# 1_V2.net
KiCad netlist of a schematic drawn in Altium Designer
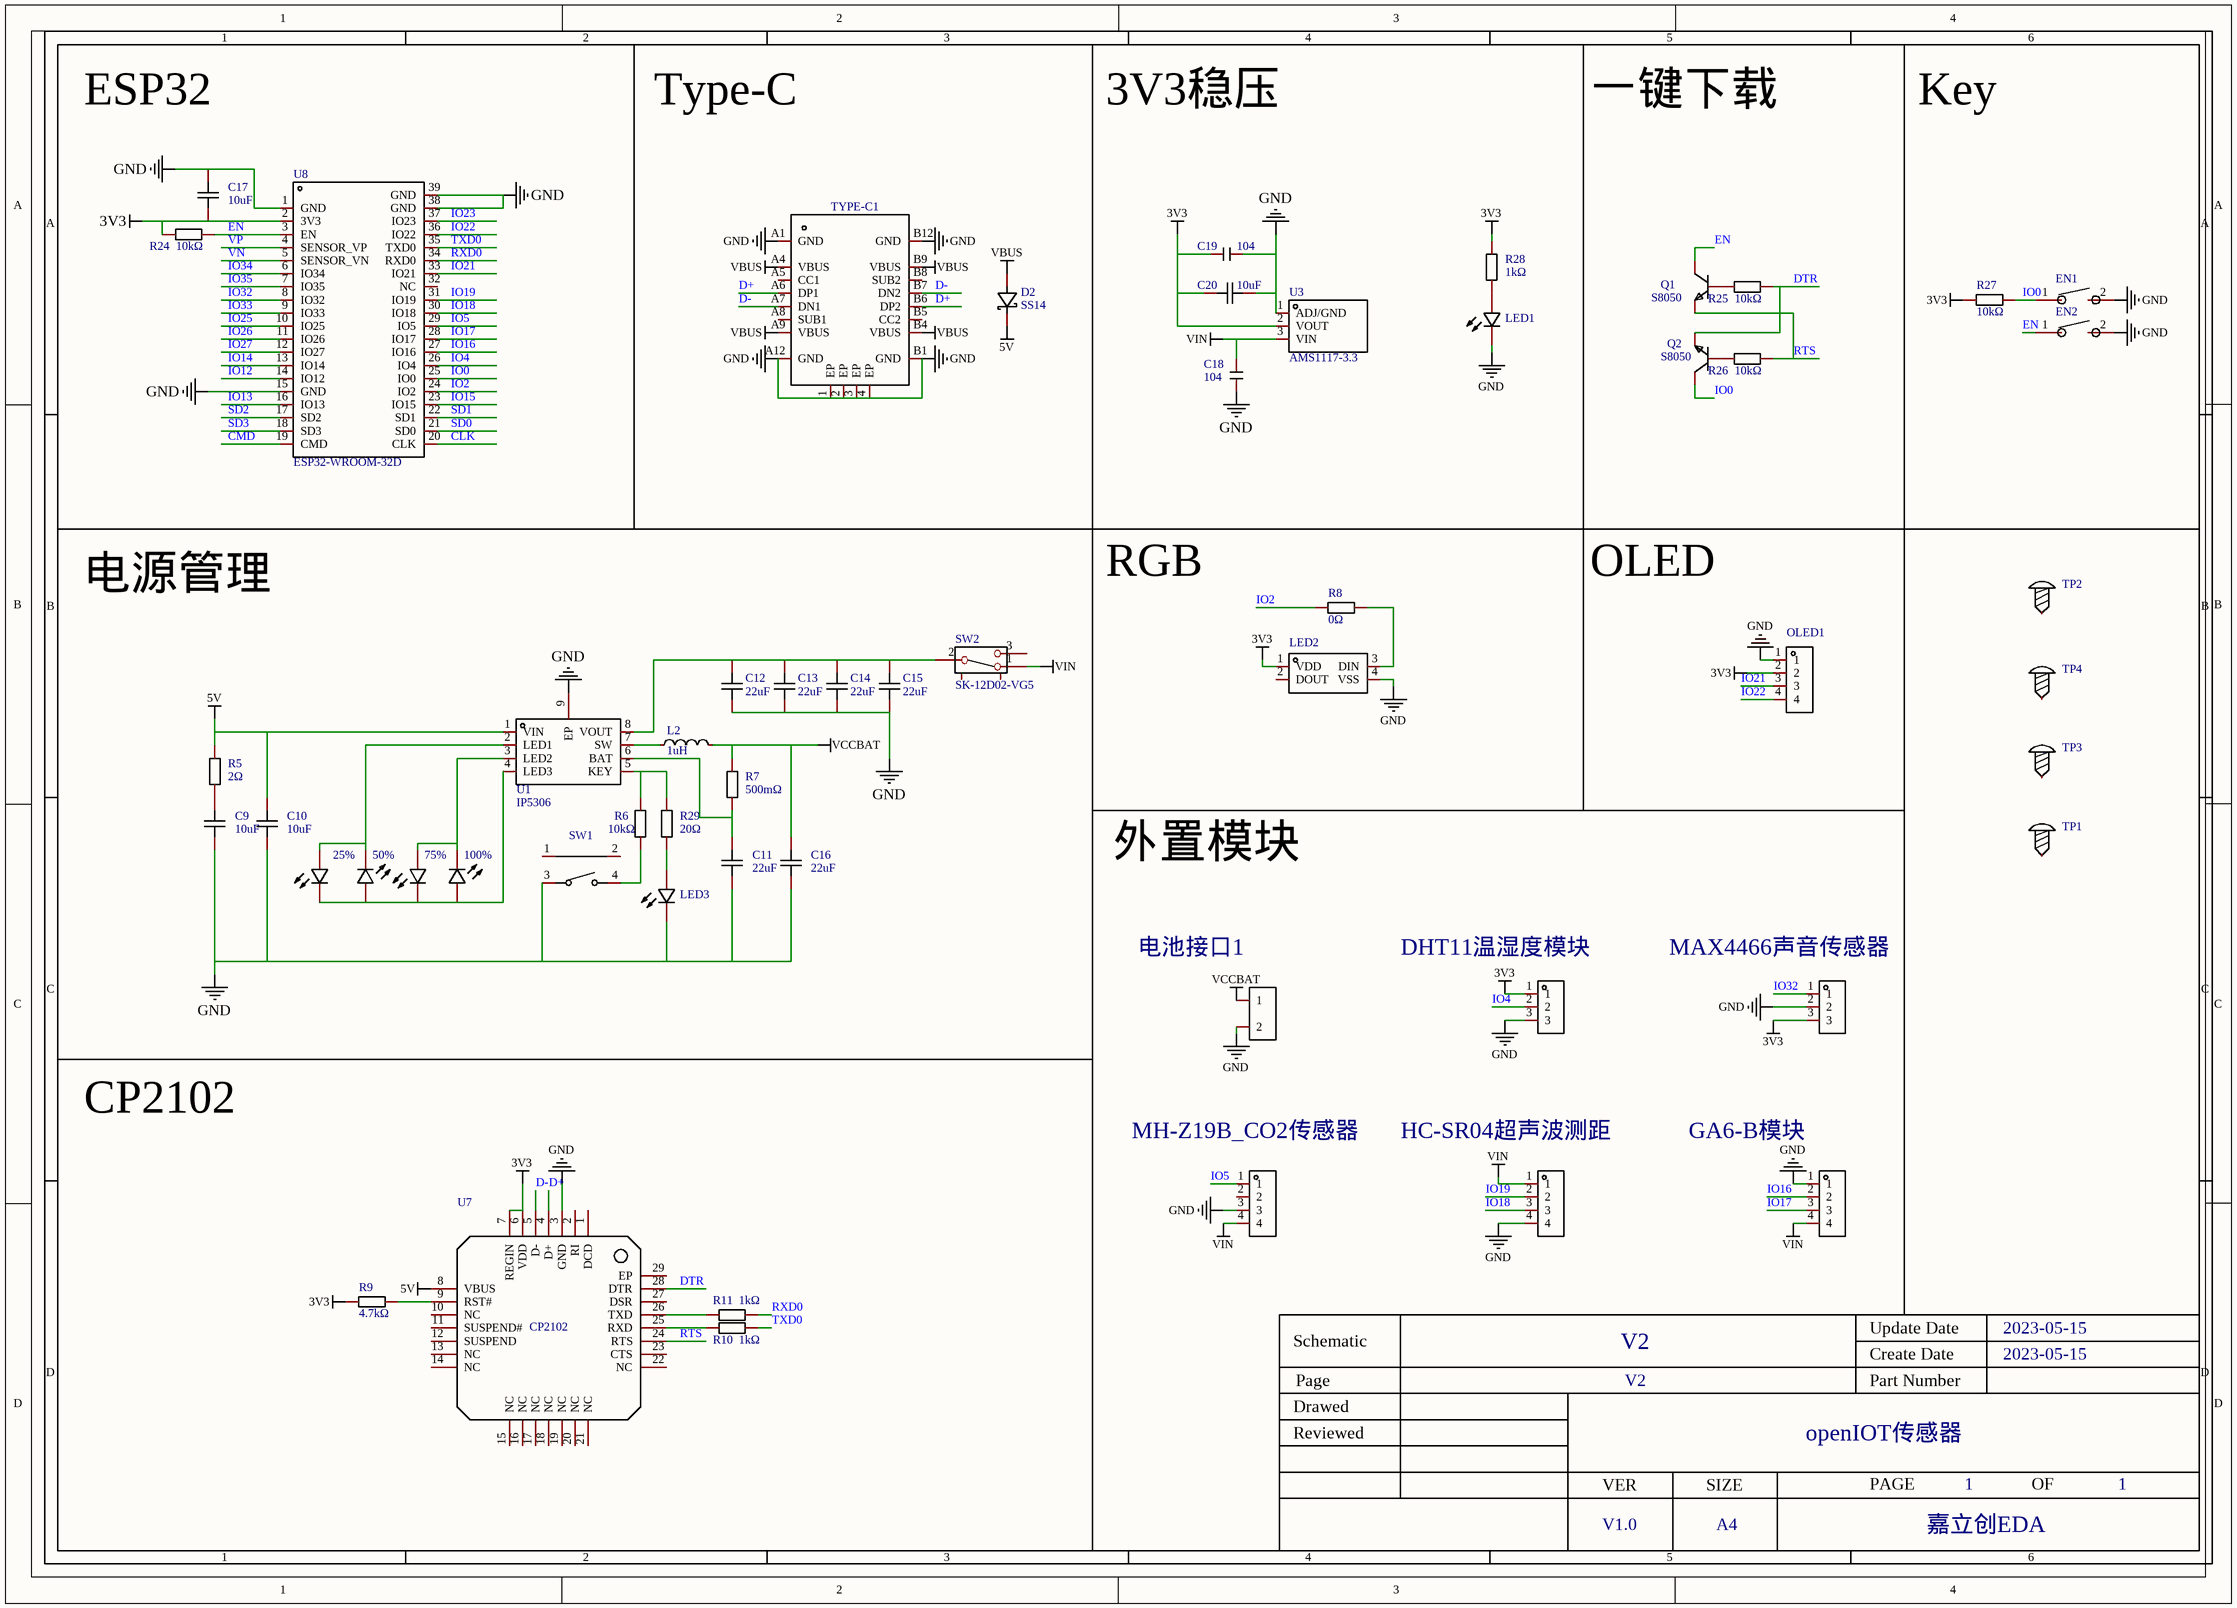
[diagram p0: 1_V2.schdoc]

(export (version "E")
  (design (tool "Eeschema 10.0.6"))
  (components
    (comp (ref "25%")
      (value "19-217/GHC-YR1S2/3T")
      (description "发光颜色:翠绿;二极管配置:-;主波长:520nm~535nm;色温:-;功率:110mW;安装方式:-;")
      (fields (field (name "MANUFACTURER") "EVERLIGHT(亿光)"))
      (libsource (lib "altium-import") (part "root_1_19-217/GHC-YR1S2/3T_"))
    )
    (comp (ref "50%")
      (value "19-217/GHC-YR1S2/3T")
      (description "发光颜色:翠绿;二极管配置:-;主波长:520nm~535nm;色温:-;功率:110mW;安装方式:-;")
      (fields (field (name "MANUFACTURER") "EVERLIGHT(亿光)"))
      (libsource (lib "altium-import") (part "root_3_19-217/GHC-YR1S2/3T_"))
    )
    (comp (ref "75%")
      (value "19-217/GHC-YR1S2/3T")
      (description "发光颜色:翠绿;二极管配置:-;主波长:520nm~535nm;色温:-;功率:110mW;安装方式:-;")
      (fields (field (name "MANUFACTURER") "EVERLIGHT(亿光)"))
      (libsource (lib "altium-import") (part "root_1_19-217/GHC-YR1S2/3T_"))
    )
    (comp (ref "100%")
      (value "19-217/GHC-YR1S2/3T")
      (description "发光颜色:翠绿;二极管配置:-;主波长:520nm~535nm;色温:-;功率:110mW;安装方式:-;")
      (fields (field (name "MANUFACTURER") "EVERLIGHT(亿光)"))
      (libsource (lib "altium-import") (part "root_3_19-217/GHC-YR1S2/3T_"))
    )
    (comp (ref "C9")
      (value "10uF")
      (description "容值:10uF;精度:±10%;额定电压:50V;材质(温度系数):X5R;")
      (fields
        (field (name "NAME") "10uF")
        (field (name "MANUFACTURER") "muRata(村田)")
        (field (name "MANUFACTURER PART") "GRM21BR61H106KE43L")
      )
      (libsource (lib "altium-import") (part "root_1_GRM21BR61H106KE43L_"))
    )
    (comp (ref "C10")
      (value "10uF")
      (description "容值:10uF;精度:±10%;额定电压:50V;材质(温度系数):X5R;")
      (fields
        (field (name "NAME") "10uF")
        (field (name "MANUFACTURER") "muRata(村田)")
        (field (name "MANUFACTURER PART") "GRM21BR61H106KE43L")
      )
      (libsource (lib "altium-import") (part "root_1_GRM21BR61H106KE43L_"))
    )
    (comp (ref "C11")
      (value "22uF")
      (description "容值:22uF;精度:±20%;额定电压:35V;材质(温度系数):X5R;")
      (fields
        (field (name "NAME") "22uF")
        (field (name "MANUFACTURER") "TDK")
        (field (name "MANUFACTURER PART") "C3216X5R1V226MTJ00E")
      )
      (libsource (lib "altium-import") (part "root_0_C3216X5R1V226MTJ00E_"))
    )
    (comp (ref "C12")
      (value "22uF")
      (description "容值:22uF;精度:±20%;额定电压:35V;材质(温度系数):X5R;")
      (fields
        (field (name "NAME") "22uF")
        (field (name "MANUFACTURER") "TDK")
        (field (name "MANUFACTURER PART") "C3216X5R1V226MTJ00E")
      )
      (libsource (lib "altium-import") (part "root_0_C3216X5R1V226MTJ00E_"))
    )
    (comp (ref "C13")
      (value "22uF")
      (description "容值:22uF;精度:±20%;额定电压:35V;材质(温度系数):X5R;")
      (fields
        (field (name "NAME") "22uF")
        (field (name "MANUFACTURER") "TDK")
        (field (name "MANUFACTURER PART") "C3216X5R1V226MTJ00E")
      )
      (libsource (lib "altium-import") (part "root_0_C3216X5R1V226MTJ00E_"))
    )
    (comp (ref "C14")
      (value "22uF")
      (description "容值:22uF;精度:±20%;额定电压:35V;材质(温度系数):X5R;")
      (fields
        (field (name "NAME") "22uF")
        (field (name "MANUFACTURER") "TDK")
        (field (name "MANUFACTURER PART") "C3216X5R1V226MTJ00E")
      )
      (libsource (lib "altium-import") (part "root_0_C3216X5R1V226MTJ00E_"))
    )
    (comp (ref "C15")
      (value "22uF")
      (description "容值:22uF;精度:±20%;额定电压:35V;材质(温度系数):X5R;")
      (fields
        (field (name "NAME") "22uF")
        (field (name "MANUFACTURER") "TDK")
        (field (name "MANUFACTURER PART") "C3216X5R1V226MTJ00E")
      )
      (libsource (lib "altium-import") (part "root_0_C3216X5R1V226MTJ00E_"))
    )
    (comp (ref "C16")
      (value "22uF")
      (description "容值:22uF;精度:±20%;额定电压:35V;材质(温度系数):X5R;")
      (fields
        (field (name "NAME") "22uF")
        (field (name "MANUFACTURER") "TDK")
        (field (name "MANUFACTURER PART") "C3216X5R1V226MTJ00E")
      )
      (libsource (lib "altium-import") (part "root_0_C3216X5R1V226MTJ00E_"))
    )
    (comp (ref "C17")
      (value "10uF")
      (description "容值:10uF;精度:±10%;额定电压:50V;材质(温度系数):X5R;")
      (fields
        (field (name "NAME") "10uF")
        (field (name "MANUFACTURER") "muRata(村田)")
        (field (name "MANUFACTURER PART") "GRM21BR61H106KE43L")
      )
      (libsource (lib "altium-import") (part "root_1_GRM21BR61H106KE43L_"))
    )
    (comp (ref "C18")
      (value "104")
      (fields (field (name "NAME") "104") (field (name "版权归属") "源创客"))
      (libsource (lib "altium-import") (part "root_1_104_"))
    )
    (comp (ref "C19")
      (value "104")
      (fields (field (name "NAME") "104") (field (name "版权归属") "源创客"))
      (libsource (lib "altium-import") (part "root_2_104_"))
    )
    (comp (ref "C20")
      (value "10uF")
      (description "容值:10uF;精度:±10%;额定电压:50V;材质(温度系数):X5R;")
      (fields
        (field (name "NAME") "10uF")
        (field (name "MANUFACTURER") "muRata(村田)")
        (field (name "MANUFACTURER PART") "GRM21BR61H106KE43L")
      )
      (libsource (lib "altium-import") (part "root_2_GRM21BR61H106KE43L_"))
    )
    (comp (ref "D2")
      (value "SS14")
      (description "二极管配置:-;直流反向耐压(Vr):40V;平均整流电流(Io):1A;正向压降(Vf):550mV@1A;反向电流(Ir):500uA@40V;")
      (fields (field (name "NAME") "SS14") (field (name "MANUFACTURER") "KUU"))
      (libsource (lib "altium-import") (part "root_1_SS14_C2909920_"))
    )
    (comp (ref "DHT11温湿度模块")
      (value "B-2200S03P-A120")
      (description "排数:单排;总孔位数:3;间距:2.54mm;插孔结构:1x3P;行距:-;安装类型:直插;塑高:-;触头材质:黄铜;触头镀层:-;")
      (fields (field (name "MANUFACTURER") "Ckmtw(灿科盟)"))
      (libsource (lib "altium-import") (part "root_0_B-2200S03P-A120_"))
    )
    (comp (ref "EN1")
      (value "TSA343G00-250J2")
      (fields (field (name "MANUFACTURER") "BRIGHT(博瑞泰)"))
      (libsource (lib "altium-import") (part "root_0_TSA343G00-250J2_"))
    )
    (comp (ref "EN2")
      (value "TSA343G00-250J2")
      (fields (field (name "MANUFACTURER") "BRIGHT(博瑞泰)"))
      (libsource (lib "altium-import") (part "root_0_TSA343G00-250J2_"))
    )
    (comp (ref "GA6-B模块")
      (value "2.54-1*4P母")
      (fields (field (name "MANUFACTURER") "BOOMELE(博穆精密)"))
      (libsource (lib "altium-import") (part "root_0_2.54-1*4P母_"))
    )
    (comp (ref "HC-SR04超声波测距")
      (value "2.54-1*4P母")
      (fields (field (name "MANUFACTURER") "BOOMELE(博穆精密)"))
      (libsource (lib "altium-import") (part "root_0_2.54-1*4P母_"))
    )
    (comp (ref "L2")
      (value "1uH")
      (description "电感值:1uH;精度:±20%;额定电流:8.5A;饱和电流(Isat):14A;")
      (fields
        (field (name "NAME") "1uH")
        (field (name "MANUFACTURER") "cjiang(长江微电)")
        (field (name "MANUFACTURER PART") "FXL0618-1R0-M")
      )
      (libsource (lib "altium-import") (part "root_0_FXL0618-1R0-M_"))
    )
    (comp (ref "LED1")
      (value "19-217/GHC-YR1S2/3T")
      (description "发光颜色:翠绿;二极管配置:-;主波长:520nm~535nm;色温:-;功率:110mW;安装方式:-;")
      (fields (field (name "MANUFACTURER") "EVERLIGHT(亿光)"))
      (libsource (lib "altium-import") (part "root_1_19-217/GHC-YR1S2/3T_"))
    )
    (comp (ref "LED2")
      (value "WS2812B-V5/W")
      (fields (field (name "MANUFACTURER") "worldsemi"))
      (libsource (lib "altium-import") (part "root_0_WS2812B-V5/W_"))
    )
    (comp (ref "LED3")
      (value "19-217/GHC-YR1S2/3T")
      (description "发光颜色:翠绿;二极管配置:-;主波长:520nm~535nm;色温:-;功率:110mW;安装方式:-;")
      (fields (field (name "MANUFACTURER") "EVERLIGHT(亿光)"))
      (libsource (lib "altium-import") (part "root_1_19-217/GHC-YR1S2/3T_"))
    )
    (comp (ref "MAX4466声音传感器")
      (value "B-2200S03P-A120")
      (description "排数:单排;总孔位数:3;间距:2.54mm;插孔结构:1x3P;行距:-;安装类型:直插;塑高:-;触头材质:黄铜;触头镀层:-;")
      (fields (field (name "MANUFACTURER") "Ckmtw(灿科盟)"))
      (libsource (lib "altium-import") (part "root_0_B-2200S03P-A120_"))
    )
    (comp (ref "MH-Z19B_CO2传感器")
      (value "2.54-1*4P母")
      (fields (field (name "MANUFACTURER") "BOOMELE(博穆精密)"))
      (libsource (lib "altium-import") (part "root_0_2.54-1*4P母_"))
    )
    (comp (ref "OLED1")
      (value "2.54-1*4P母")
      (fields (field (name "MANUFACTURER") "BOOMELE(博穆精密)"))
      (libsource (lib "altium-import") (part "root_0_2.54-1*4P母_"))
    )
    (comp (ref "Q1")
      (value "S8050")
      (fields (field (name "NAME") "S8050") (field (name "MANUFACTURER") "WPMtek(维攀微)"))
      (libsource (lib "altium-import") (part "root_0_S8050_"))
    )
    (comp (ref "Q2")
      (value "S8050")
      (fields (field (name "NAME") "S8050") (field (name "MANUFACTURER") "WPMtek(维攀微)"))
      (libsource (lib "altium-import") (part "root_2_S8050_"))
    )
    (comp (ref "R5")
      (value "2Ω")
      (description "电阻类型:厚膜电阻;阻值:2Ω;精度:±1%;功率:125mW;")
      (fields
        (field (name "NAME") "2Ω")
        (field (name "MANUFACTURER") "UNI-ROYAL(厚声)")
        (field (name "MANUFACTURER PART") "0805W8F200KT5E")
      )
      (libsource (lib "altium-import") (part "root_1_0805W8F200KT5E_"))
    )
    (comp (ref "R6")
      (value "10kΩ")
      (description "电阻类型:厚膜电阻;阻值:10kΩ;精度:±1%;功率:125mW;")
      (fields
        (field (name "NAME") "10kΩ")
        (field (name "MANUFACTURER") "UNI-ROYAL(厚声)")
        (field (name "MANUFACTURER PART") "0805W8F1002T5E")
      )
      (libsource (lib "altium-import") (part "root_1_0805W8F1002T5E_C17414_"))
    )
    (comp (ref "R7")
      (value "500mΩ")
      (description "电阻类型:厚膜电阻;阻值:500mΩ;精度:±1%;功率:250mW;")
      (fields
        (field (name "NAME") "500mΩ")
        (field (name "MANUFACTURER") "UNI-ROYAL(厚声)")
        (field (name "MANUFACTURER PART") "1206W4F500LT5E")
      )
      (libsource (lib "altium-import") (part "root_1_1206W4F500LT5E_"))
    )
    (comp (ref "R8")
      (value "0Ω")
      (description "电阻类型:厚膜电阻;阻值:0Ω;精度:±1%;功率:100mW;最大工作电压:75V;工作温度范围:-55℃~+155℃;")
      (fields
        (field (name "MANUFACTURER") "UNI-ROYAL(厚声)")
        (field (name "MANUFACTURER PART") "0603WAF0000T5E")
      )
      (libsource (lib "altium-import") (part "root_2_0603WAF0000T5E_"))
    )
    (comp (ref "R9")
      (value "4.7kΩ")
      (description "电阻类型:厚膜电阻;阻值:4.7kΩ;精度:±1%;功率:100mW;")
      (fields
        (field (name "NAME") "4.7kΩ")
        (field (name "MANUFACTURER") "UNI-ROYAL(厚声)")
        (field (name "MANUFACTURER PART") "0603WAF4701T5E")
      )
      (libsource (lib "altium-import") (part "root_0_0603WAF4701T5E_"))
    )
    (comp (ref "R10")
      (value "1kΩ")
      (description "电阻类型:厚膜电阻;阻值:1kΩ;精度:±1%;功率:100mW;")
      (fields
        (field (name "NAME") "1kΩ")
        (field (name "MANUFACTURER") "UNI-ROYAL(厚声)")
        (field (name "MANUFACTURER PART") "0603WAF1001T5E")
      )
      (libsource (lib "altium-import") (part "root_0_0603WAF1001T5E_"))
    )
    (comp (ref "R11")
      (value "1kΩ")
      (description "电阻类型:厚膜电阻;阻值:1kΩ;精度:±1%;功率:100mW;")
      (fields
        (field (name "NAME") "1kΩ")
        (field (name "MANUFACTURER") "UNI-ROYAL(厚声)")
        (field (name "MANUFACTURER PART") "0603WAF1001T5E")
      )
      (libsource (lib "altium-import") (part "root_0_0603WAF1001T5E_"))
    )
    (comp (ref "R24")
      (value "10kΩ")
      (description "电阻类型:厚膜电阻;阻值:10kΩ;精度:±1%;功率:100mW;")
      (fields
        (field (name "NAME") "10kΩ")
        (field (name "MANUFACTURER") "UNI-ROYAL(厚声)")
        (field (name "MANUFACTURER PART") "0603WAF1002T5E")
      )
      (libsource (lib "altium-import") (part "root_0_0603WAF1002T5E_"))
    )
    (comp (ref "R25")
      (value "10kΩ")
      (description "电阻类型:厚膜电阻;阻值:10kΩ;精度:±1%;功率:100mW;")
      (fields
        (field (name "NAME") "10kΩ")
        (field (name "MANUFACTURER") "UNI-ROYAL(厚声)")
        (field (name "MANUFACTURER PART") "0603WAF1002T5E")
      )
      (libsource (lib "altium-import") (part "root_0_0603WAF1002T5E_"))
    )
    (comp (ref "R26")
      (value "10kΩ")
      (description "电阻类型:厚膜电阻;阻值:10kΩ;精度:±1%;功率:100mW;")
      (fields
        (field (name "NAME") "10kΩ")
        (field (name "MANUFACTURER") "UNI-ROYAL(厚声)")
        (field (name "MANUFACTURER PART") "0603WAF1002T5E")
      )
      (libsource (lib "altium-import") (part "root_0_0603WAF1002T5E_"))
    )
    (comp (ref "R27")
      (value "10kΩ")
      (description "电阻类型:厚膜电阻;阻值:10kΩ;精度:±1%;功率:100mW;")
      (fields
        (field (name "NAME") "10kΩ")
        (field (name "MANUFACTURER") "UNI-ROYAL(厚声)")
        (field (name "MANUFACTURER PART") "0603WAF1002T5E")
      )
      (libsource (lib "altium-import") (part "root_2_0603WAF1002T5E_"))
    )
    (comp (ref "R28")
      (value "1kΩ")
      (description "电阻类型:厚膜电阻;阻值:1kΩ;精度:±1%;功率:100mW;")
      (fields
        (field (name "NAME") "1kΩ")
        (field (name "MANUFACTURER") "UNI-ROYAL(厚声)")
        (field (name "MANUFACTURER PART") "0603WAF1001T5E")
      )
      (libsource (lib "altium-import") (part "root_1_0603WAF1001T5E_"))
    )
    (comp (ref "R29")
      (value "20Ω")
      (description "电阻类型:厚膜电阻;阻值:20Ω;精度:±1%;功率:100mW;")
      (fields
        (field (name "NAME") "20Ω")
        (field (name "MANUFACTURER") "UNI-ROYAL(厚声)")
        (field (name "MANUFACTURER PART") "0603WAF200JT5E")
      )
      (libsource (lib "altium-import") (part "root_1_0603WAF200JT5E_"))
    )
    (comp (ref "SW1")
      (value "TS24CA")
      (description "触点电流:50mA;额定电压(DC):12V;电路结构:单刀单掷;安装方式:卧贴;带灯:-;机械寿命:-;")
      (fields (field (name "MANUFACTURER") "SHOU HAN(首韩)"))
      (libsource (lib "altium-import") (part "root_0_TS24CA_"))
    )
    (comp (ref "SW2")
      (value "SK-12D02-VG5")
      (fields (field (name "NAME") "SK-12D02-VG5") (field (name "MANUFACTURER") "韩国韩荣"))
      (libsource (lib "altium-import") (part "root_0_SK-12D02-VG5_C136722_"))
    )
    (comp (ref "TP1") (value "M2螺丝") (libsource (lib "altium-import") (part "root_0_M2螺丝_")))
    (comp (ref "TP2") (value "M2螺丝") (libsource (lib "altium-import") (part "root_0_M2螺丝_")))
    (comp (ref "TP3") (value "M2螺丝") (libsource (lib "altium-import") (part "root_0_M2螺丝_")))
    (comp (ref "TP4") (value "M2螺丝") (libsource (lib "altium-import") (part "root_0_M2螺丝_")))
    (comp (ref "TYPE-C1")
      (value "KH-TYPE-C-16P")
      (description "连接器类型:Type-C;标准:-;公母:母座;触点数量:16;端口数量:1;安装方式:卧贴;额定电流 - 电源:3A;工作温度范围:-40℃~+85℃;")
      (fields (field (name "MANUFACTURER") "kinghelm(金航标)"))
      (libsource (lib "altium-import") (part "root_0_KH-TYPE-C-16P_"))
    )
    (comp (ref "U1")
      (value "IP5306")
      (description "2.1A充电2.4A放电高集成度移动电源SOC")
      (fields (field (name "NAME") "IP5306") (field (name "MANUFACTURER") "INJOINIC(英集芯)"))
      (libsource (lib "altium-import") (part "root_0_IP5306_"))
    )
    (comp (ref "U3")
      (value "AMS1117-3.3")
      (description "输出类型:-;")
      (fields (field (name "NAME") "AMS1117-3.3") (field (name "MANUFACTURER") "Slkor(萨科微)"))
      (libsource (lib "altium-import") (part "root_0_AMS1117-3.3_C880752_"))
    )
    (comp (ref "U7")
      (value "CP2102")
      (description "类型:Transceiver;协议类别:USB;驱动器/接收器数:1/1;数据速率:1Mbps;")
      (fields (field (name "NAME") "CP2102") (field (name "MANUFACTURER") "SILICON LABS(芯科)"))
      (libsource (lib "altium-import") (part "root_3_CP2102-GMR_"))
    )
    (comp (ref "U8")
      (value "ESP32-WROOM-32D")
      (fields (field (name "NAME") "ESP32-WROOM-32D"))
      (libsource (lib "altium-import") (part "root_0_ESP32-WROOM-32D_"))
    )
    (comp (ref "电池接口1")
      (value "826629-2")
      (fields (field (name "MANUFACTURER") "TE Connectivity(美国泰科)"))
      (libsource (lib "altium-import") (part "root_0_826629-2_"))
    )
  )
  (nets
    (net (code "1") (name "/CLK") (class "Default")
      (node (ref "U8") (pin "20") (pinfunction "CLK_20") (pintype "passive"))
    )
    (net (code "2") (name "/CMD") (class "Default")
      (node (ref "U8") (pin "19") (pinfunction "CMD_19") (pintype "passive"))
    )
    (net (code "3") (name "/D+") (class "Default")
      (node (ref "TYPE-C1") (pin "A6") (pinfunction "DP1_A6") (pintype "passive"))
      (node (ref "TYPE-C1") (pin "B6") (pinfunction "DP2_B6") (pintype "passive"))
      (node (ref "U7") (pin "4") (pinfunction "D+_4") (pintype "passive"))
    )
    (net (code "4") (name "/D-") (class "Default")
      (node (ref "TYPE-C1") (pin "A7") (pinfunction "DN1_A7") (pintype "passive"))
      (node (ref "TYPE-C1") (pin "B7") (pinfunction "DN2_B7") (pintype "passive"))
      (node (ref "U7") (pin "5") (pinfunction "D-_5") (pintype "passive"))
    )
    (net (code "5") (name "/DTR") (class "Default")
      (node (ref "Q2") (pin "2") (pinfunction "E_2") (pintype "passive"))
      (node (ref "R25") (pin "2") (pinfunction "2_2") (pintype "passive"))
      (node (ref "U7") (pin "28") (pinfunction "DTR_28") (pintype "passive"))
    )
    (net (code "6") (name "/EN") (class "Default")
      (node (ref "EN2") (pin "1") (pinfunction "1_1") (pintype "passive"))
      (node (ref "Q1") (pin "3") (pinfunction "C_3") (pintype "passive"))
      (node (ref "R24") (pin "2") (pinfunction "2_2") (pintype "passive"))
      (node (ref "U8") (pin "3") (pinfunction "EN_3") (pintype "passive"))
    )
    (net (code "7") (name "/IO0") (class "Default")
      (node (ref "EN1") (pin "1") (pinfunction "1_1") (pintype "passive"))
      (node (ref "Q2") (pin "3") (pinfunction "C_3") (pintype "passive"))
      (node (ref "R27") (pin "1") (pinfunction "1_1") (pintype "passive"))
      (node (ref "U8") (pin "25") (pinfunction "IO0_25") (pintype "passive"))
    )
    (net (code "8") (name "/IO2") (class "Default")
      (node (ref "R8") (pin "2") (pinfunction "2_2") (pintype "passive"))
      (node (ref "U8") (pin "24") (pinfunction "IO2_24") (pintype "passive"))
    )
    (net (code "9") (name "/IO4") (class "Default")
      (node (ref "DHT11温湿度模块") (pin "2") (pinfunction "2_2") (pintype "passive"))
      (node (ref "U8") (pin "26") (pinfunction "IO4_26") (pintype "passive"))
    )
    (net (code "10") (name "/IO5") (class "Default")
      (node (ref "MH-Z19B_CO2传感器") (pin "1") (pinfunction "1_1") (pintype "passive"))
      (node (ref "U8") (pin "29") (pinfunction "IO5_29") (pintype "passive"))
    )
    (net (code "11") (name "/IO12") (class "Default")
      (node (ref "U8") (pin "14") (pinfunction "IO12_14") (pintype "passive"))
    )
    (net (code "12") (name "/IO13") (class "Default")
      (node (ref "U8") (pin "16") (pinfunction "IO13_16") (pintype "passive"))
    )
    (net (code "13") (name "/IO14") (class "Default")
      (node (ref "U8") (pin "13") (pinfunction "IO14_13") (pintype "passive"))
    )
    (net (code "14") (name "/IO15") (class "Default")
      (node (ref "U8") (pin "23") (pinfunction "IO15_23") (pintype "passive"))
    )
    (net (code "15") (name "/IO16") (class "Default")
      (node (ref "GA6-B模块") (pin "2") (pinfunction "2_2") (pintype "passive"))
      (node (ref "U8") (pin "27") (pinfunction "IO16_27") (pintype "passive"))
    )
    (net (code "16") (name "/IO17") (class "Default")
      (node (ref "GA6-B模块") (pin "3") (pinfunction "3_3") (pintype "passive"))
      (node (ref "U8") (pin "28") (pinfunction "IO17_28") (pintype "passive"))
    )
    (net (code "17") (name "/IO18") (class "Default")
      (node (ref "HC-SR04超声波测距") (pin "3") (pinfunction "3_3") (pintype "passive"))
      (node (ref "U8") (pin "30") (pinfunction "IO18_30") (pintype "passive"))
    )
    (net (code "18") (name "/IO19") (class "Default")
      (node (ref "HC-SR04超声波测距") (pin "2") (pinfunction "2_2") (pintype "passive"))
      (node (ref "U8") (pin "31") (pinfunction "IO19_31") (pintype "passive"))
    )
    (net (code "19") (name "/IO21") (class "Default")
      (node (ref "OLED1") (pin "3") (pinfunction "3_3") (pintype "passive"))
      (node (ref "U8") (pin "33") (pinfunction "IO21_33") (pintype "passive"))
    )
    (net (code "20") (name "/IO22") (class "Default")
      (node (ref "OLED1") (pin "4") (pinfunction "4_4") (pintype "passive"))
      (node (ref "U8") (pin "36") (pinfunction "IO22_36") (pintype "passive"))
    )
    (net (code "21") (name "/IO23") (class "Default")
      (node (ref "U8") (pin "37") (pinfunction "IO23_37") (pintype "passive"))
    )
    (net (code "22") (name "/IO25") (class "Default")
      (node (ref "U8") (pin "10") (pinfunction "IO25_10") (pintype "passive"))
    )
    (net (code "23") (name "/IO26") (class "Default")
      (node (ref "U8") (pin "11") (pinfunction "IO26_11") (pintype "passive"))
    )
    (net (code "24") (name "/IO27") (class "Default")
      (node (ref "U8") (pin "12") (pinfunction "IO27_12") (pintype "passive"))
    )
    (net (code "25") (name "/IO32") (class "Default")
      (node (ref "MAX4466声音传感器") (pin "1") (pinfunction "1_1") (pintype "passive"))
      (node (ref "U8") (pin "8") (pinfunction "IO32_8") (pintype "passive"))
    )
    (net (code "26") (name "/IO33") (class "Default")
      (node (ref "U8") (pin "9") (pinfunction "IO33_9") (pintype "passive"))
    )
    (net (code "27") (name "/IO34") (class "Default")
      (node (ref "U8") (pin "6") (pinfunction "IO34_6") (pintype "passive"))
    )
    (net (code "28") (name "/IO35") (class "Default")
      (node (ref "U8") (pin "7") (pinfunction "IO35_7") (pintype "passive"))
    )
    (net (code "29") (name "/RTS") (class "Default")
      (node (ref "Q1") (pin "2") (pinfunction "E_2") (pintype "passive"))
      (node (ref "R26") (pin "2") (pinfunction "2_2") (pintype "passive"))
      (node (ref "U7") (pin "24") (pinfunction "RTS_24") (pintype "passive"))
    )
    (net (code "30") (name "/RXD0") (class "Default")
      (node (ref "R11") (pin "2") (pinfunction "2_2") (pintype "passive"))
      (node (ref "U8") (pin "34") (pinfunction "RXD0_34") (pintype "passive"))
    )
    (net (code "31") (name "/SD0") (class "Default")
      (node (ref "U8") (pin "21") (pinfunction "SD0_21") (pintype "passive"))
    )
    (net (code "32") (name "/SD1") (class "Default")
      (node (ref "U8") (pin "22") (pinfunction "SD1_22") (pintype "passive"))
    )
    (net (code "33") (name "/SD2") (class "Default")
      (node (ref "U8") (pin "17") (pinfunction "SD2_17") (pintype "passive"))
    )
    (net (code "34") (name "/SD3") (class "Default")
      (node (ref "U8") (pin "18") (pinfunction "SD3_18") (pintype "passive"))
    )
    (net (code "35") (name "/TXD0") (class "Default")
      (node (ref "R10") (pin "2") (pinfunction "2_2") (pintype "passive"))
      (node (ref "U8") (pin "35") (pinfunction "TXD0_35") (pintype "passive"))
    )
    (net (code "36") (name "/VN") (class "Default")
      (node (ref "U8") (pin "5") (pinfunction "SENSOR_VN_5") (pintype "passive"))
    )
    (net (code "37") (name "/VP") (class "Default")
      (node (ref "U8") (pin "4") (pinfunction "SENSOR_VP_4") (pintype "passive"))
    )
    (net (code "38") (name "3V3") (class "Default")
      (node (ref "C17") (pin "1") (pinfunction "1_1") (pintype "passive"))
      (node (ref "C19") (pin "2") (pinfunction "2_2") (pintype "passive"))
      (node (ref "C20") (pin "2") (pinfunction "2_2") (pintype "passive"))
      (node (ref "DHT11温湿度模块") (pin "1") (pinfunction "1_1") (pintype "passive"))
      (node (ref "LED2") (pin "1") (pinfunction "VDD_1") (pintype "passive"))
      (node (ref "MAX4466声音传感器") (pin "3") (pinfunction "3_3") (pintype "passive"))
      (node (ref "OLED1") (pin "2") (pinfunction "2_2") (pintype "passive"))
      (node (ref "R24") (pin "1") (pinfunction "1_1") (pintype "passive"))
      (node (ref "R27") (pin "2") (pinfunction "2_2") (pintype "passive"))
      (node (ref "R28") (pin "2") (pinfunction "2_2") (pintype "passive"))
      (node (ref "R9") (pin "1") (pinfunction "1_1") (pintype "passive"))
      (node (ref "U3") (pin "2") (pinfunction "VOUT_2") (pintype "passive"))
      (node (ref "U7") (pin "6") (pinfunction "VDD_6") (pintype "passive"))
      (node (ref "U7") (pin "7") (pinfunction "REGIN_7") (pintype "passive"))
      (node (ref "U8") (pin "2") (pinfunction "3V3_2") (pintype "passive"))
    )
    (net (code "39") (name "5V") (class "Default")
      (node (ref "C10") (pin "2") (pinfunction "2_2") (pintype "passive"))
      (node (ref "D2") (pin "1") (pinfunction "A_1") (pintype "passive"))
      (node (ref "R5") (pin "2") (pinfunction "2_2") (pintype "passive"))
      (node (ref "U1") (pin "1") (pinfunction "VIN_1") (pintype "passive"))
      (node (ref "U7") (pin "8") (pinfunction "VBUS_8") (pintype "passive"))
    )
    (net (code "40") (name "GND") (class "Default")
      (node (ref "C10") (pin "1") (pinfunction "1_1") (pintype "passive"))
      (node (ref "C11") (pin "1") (pinfunction "1_1") (pintype "passive"))
      (node (ref "C12") (pin "1") (pinfunction "1_1") (pintype "passive"))
      (node (ref "C13") (pin "1") (pinfunction "1_1") (pintype "passive"))
      (node (ref "C14") (pin "1") (pinfunction "1_1") (pintype "passive"))
      (node (ref "C15") (pin "1") (pinfunction "1_1") (pintype "passive"))
      (node (ref "C16") (pin "1") (pinfunction "1_1") (pintype "passive"))
      (node (ref "C17") (pin "2") (pinfunction "2_2") (pintype "passive"))
      (node (ref "C18") (pin "1") (pinfunction "1_1") (pintype "passive"))
      (node (ref "C19") (pin "1") (pinfunction "1_1") (pintype "passive"))
      (node (ref "C20") (pin "1") (pinfunction "1_1") (pintype "passive"))
      (node (ref "C9") (pin "1") (pinfunction "1_1") (pintype "passive"))
      (node (ref "DHT11温湿度模块") (pin "3") (pinfunction "3_3") (pintype "passive"))
      (node (ref "EN1") (pin "2") (pinfunction "2_2") (pintype "passive"))
      (node (ref "EN2") (pin "2") (pinfunction "2_2") (pintype "passive"))
      (node (ref "GA6-B模块") (pin "1") (pinfunction "1_1") (pintype "passive"))
      (node (ref "HC-SR04超声波测距") (pin "4") (pinfunction "4_4") (pintype "passive"))
      (node (ref "LED1") (pin "1") (pinfunction "C_1") (pintype "passive"))
      (node (ref "LED2") (pin "4") (pinfunction "VSS_4") (pintype "passive"))
      (node (ref "LED3") (pin "1") (pinfunction "C_1") (pintype "passive"))
      (node (ref "MAX4466声音传感器") (pin "2") (pinfunction "2_2") (pintype "passive"))
      (node (ref "MH-Z19B_CO2传感器") (pin "3") (pinfunction "3_3") (pintype "passive"))
      (node (ref "OLED1") (pin "1") (pinfunction "1_1") (pintype "passive"))
      (node (ref "SW1") (pin "3") (pinfunction "3_3") (pintype "passive"))
      (node (ref "TYPE-C1") (pin "1") (pinfunction "EP_1") (pintype "passive"))
      (node (ref "TYPE-C1") (pin "2") (pinfunction "EP_2") (pintype "passive"))
      (node (ref "TYPE-C1") (pin "3") (pinfunction "EP_3") (pintype "passive"))
      (node (ref "TYPE-C1") (pin "4") (pinfunction "EP_4") (pintype "passive"))
      (node (ref "TYPE-C1") (pin "A1") (pinfunction "GND_A1") (pintype "passive"))
      (node (ref "TYPE-C1") (pin "A12") (pinfunction "GND_A12") (pintype "passive"))
      (node (ref "TYPE-C1") (pin "B1") (pinfunction "GND_B1") (pintype "passive"))
      (node (ref "TYPE-C1") (pin "B12") (pinfunction "GND_B12") (pintype "passive"))
      (node (ref "U1") (pin "9") (pinfunction "EP_9") (pintype "passive"))
      (node (ref "U3") (pin "1") (pinfunction "ADJ/GND_1") (pintype "passive"))
      (node (ref "U7") (pin "3") (pinfunction "GND_3") (pintype "passive"))
      (node (ref "U8") (pin "1") (pinfunction "GND_1") (pintype "passive"))
      (node (ref "U8") (pin "15") (pinfunction "GND_15") (pintype "passive"))
      (node (ref "U8") (pin "38") (pinfunction "GND_38") (pintype "passive"))
      (node (ref "U8") (pin "39") (pinfunction "GND_39") (pintype "passive"))
      (node (ref "电池接口1") (pin "2") (pinfunction "2_2") (pintype "passive"))
    )
    (net (code "41") (name "Net-(25%-A)") (class "Default")
      (node (ref "25%") (pin "2") (pinfunction "A_2") (pintype "passive"))
      (node (ref "50%") (pin "1") (pinfunction "C_1") (pintype "passive"))
      (node (ref "U1") (pin "2") (pinfunction "LED1_2") (pintype "passive"))
    )
    (net (code "42") (name "Net-(100%-A)") (class "Default")
      (node (ref "100%") (pin "2") (pinfunction "A_2") (pintype "passive"))
      (node (ref "25%") (pin "1") (pinfunction "C_1") (pintype "passive"))
      (node (ref "50%") (pin "2") (pinfunction "A_2") (pintype "passive"))
      (node (ref "75%") (pin "1") (pinfunction "C_1") (pintype "passive"))
      (node (ref "U1") (pin "4") (pinfunction "LED3_4") (pintype "passive"))
    )
    (net (code "43") (name "Net-(100%-C)") (class "Default")
      (node (ref "100%") (pin "1") (pinfunction "C_1") (pintype "passive"))
      (node (ref "75%") (pin "2") (pinfunction "A_2") (pintype "passive"))
      (node (ref "U1") (pin "3") (pinfunction "LED2_3") (pintype "passive"))
    )
    (net (code "44") (name "Net-(C9-Pad2)") (class "Default")
      (node (ref "C9") (pin "2") (pinfunction "2_2") (pintype "passive"))
      (node (ref "R5") (pin "1") (pinfunction "1_1") (pintype "passive"))
    )
    (net (code "45") (name "Net-(LED1-A)") (class "Default")
      (node (ref "LED1") (pin "2") (pinfunction "A_2") (pintype "passive"))
      (node (ref "R28") (pin "1") (pinfunction "1_1") (pintype "passive"))
    )
    (net (code "46") (name "Net-(LED2-DIN)") (class "Default")
      (node (ref "LED2") (pin "3") (pinfunction "DIN_3") (pintype "passive"))
      (node (ref "R8") (pin "1") (pinfunction "1_1") (pintype "passive"))
    )
    (net (code "47") (name "Net-(LED3-A)") (class "Default")
      (node (ref "LED3") (pin "2") (pinfunction "A_2") (pintype "passive"))
      (node (ref "R29") (pin "1") (pinfunction "1_1") (pintype "passive"))
    )
    (net (code "48") (name "Net-(Q1-B)") (class "Default")
      (node (ref "Q1") (pin "1") (pinfunction "B_1") (pintype "passive"))
      (node (ref "R25") (pin "1") (pinfunction "1_1") (pintype "passive"))
    )
    (net (code "49") (name "Net-(Q2-B)") (class "Default")
      (node (ref "Q2") (pin "1") (pinfunction "B_1") (pintype "passive"))
      (node (ref "R26") (pin "1") (pinfunction "1_1") (pintype "passive"))
    )
    (net (code "50") (name "Net-(R6-Pad1)") (class "Default")
      (node (ref "R6") (pin "1") (pinfunction "1_1") (pintype "passive"))
      (node (ref "SW1") (pin "4") (pinfunction "4_4") (pintype "passive"))
    )
    (net (code "51") (name "Net-(U1-BAT)") (class "Default")
      (node (ref "C11") (pin "2") (pinfunction "2_2") (pintype "passive"))
      (node (ref "R7") (pin "1") (pinfunction "1_1") (pintype "passive"))
      (node (ref "U1") (pin "6") (pinfunction "BAT_6") (pintype "passive"))
    )
    (net (code "52") (name "Net-(U1-KEY)") (class "Default")
      (node (ref "R29") (pin "2") (pinfunction "2_2") (pintype "passive"))
      (node (ref "R6") (pin "2") (pinfunction "2_2") (pintype "passive"))
      (node (ref "U1") (pin "5") (pinfunction "KEY_5") (pintype "passive"))
    )
    (net (code "53") (name "Net-(U1-SW)") (class "Default")
      (node (ref "L2") (pin "1") (pinfunction "1_1") (pintype "passive"))
      (node (ref "U1") (pin "7") (pinfunction "SW_7") (pintype "passive"))
    )
    (net (code "54") (name "Net-(U1-VOUT)") (class "Default")
      (node (ref "C12") (pin "2") (pinfunction "2_2") (pintype "passive"))
      (node (ref "C13") (pin "2") (pinfunction "2_2") (pintype "passive"))
      (node (ref "C14") (pin "2") (pinfunction "2_2") (pintype "passive"))
      (node (ref "C15") (pin "2") (pinfunction "2_2") (pintype "passive"))
      (node (ref "SW2") (pin "2") (pinfunction "2_2") (pintype "passive"))
      (node (ref "U1") (pin "8") (pinfunction "VOUT_8") (pintype "passive"))
    )
    (net (code "55") (name "Net-(U7-RST#)") (class "Default")
      (node (ref "R9") (pin "2") (pinfunction "2_2") (pintype "passive"))
      (node (ref "U7") (pin "9") (pinfunction "RST#_9") (pintype "passive"))
    )
    (net (code "56") (name "Net-(U7-RXD)") (class "Default")
      (node (ref "R10") (pin "1") (pinfunction "1_1") (pintype "passive"))
      (node (ref "U7") (pin "25") (pinfunction "RXD_25") (pintype "passive"))
    )
    (net (code "57") (name "Net-(U7-TXD)") (class "Default")
      (node (ref "R11") (pin "1") (pinfunction "1_1") (pintype "passive"))
      (node (ref "U7") (pin "26") (pinfunction "TXD_26") (pintype "passive"))
    )
    (net (code "58") (name "VBUS") (class "Default")
      (node (ref "D2") (pin "2") (pinfunction "K_2") (pintype "passive"))
      (node (ref "TYPE-C1") (pin "A4") (pinfunction "VBUS_A4") (pintype "passive"))
      (node (ref "TYPE-C1") (pin "A9") (pinfunction "VBUS_A9") (pintype "passive"))
      (node (ref "TYPE-C1") (pin "B4") (pinfunction "VBUS_B4") (pintype "passive"))
      (node (ref "TYPE-C1") (pin "B9") (pinfunction "VBUS_B9") (pintype "passive"))
    )
    (net (code "59") (name "VCCBAT") (class "Default")
      (node (ref "C16") (pin "2") (pinfunction "2_2") (pintype "passive"))
      (node (ref "L2") (pin "2") (pinfunction "2_2") (pintype "passive"))
      (node (ref "R7") (pin "2") (pinfunction "2_2") (pintype "passive"))
      (node (ref "电池接口1") (pin "1") (pinfunction "1_1") (pintype "passive"))
    )
    (net (code "60") (name "VIN") (class "Default")
      (node (ref "C18") (pin "2") (pinfunction "2_2") (pintype "passive"))
      (node (ref "GA6-B模块") (pin "4") (pinfunction "4_4") (pintype "passive"))
      (node (ref "HC-SR04超声波测距") (pin "1") (pinfunction "1_1") (pintype "passive"))
      (node (ref "MH-Z19B_CO2传感器") (pin "4") (pinfunction "4_4") (pintype "passive"))
      (node (ref "SW2") (pin "1") (pinfunction "1_1") (pintype "passive"))
      (node (ref "U3") (pin "3") (pinfunction "VIN_3") (pintype "passive"))
    )
    (net (code "61") (name "unconnected-(LED2-DOUT-Pad2)") (class "Default")
      (node (ref "LED2") (pin "2") (pinfunction "DOUT_2") (pintype "passive"))
    )
    (net (code "62") (name "unconnected-(MH-Z19B_CO2传感器-Pad2)") (class "Default")
      (node (ref "MH-Z19B_CO2传感器") (pin "2") (pinfunction "2_2") (pintype "passive"))
    )
    (net (code "63") (name "unconnected-(SW1-Pad1)") (class "Default")
      (node (ref "SW1") (pin "1") (pinfunction "1_1") (pintype "passive"))
    )
    (net (code "64") (name "unconnected-(SW1-Pad2)") (class "Default")
      (node (ref "SW1") (pin "2") (pinfunction "2_2") (pintype "passive"))
    )
    (net (code "65") (name "unconnected-(SW2-Pad3)") (class "Default")
      (node (ref "SW2") (pin "3") (pinfunction "3_3") (pintype "passive"))
    )
    (net (code "66") (name "unconnected-(SW2-Pad4)") (class "Default")
      (node (ref "SW2") (pin "4") (pinfunction "4_4") (pintype "passive"))
    )
    (net (code "67") (name "unconnected-(SW2-Pad5)") (class "Default")
      (node (ref "SW2") (pin "5") (pinfunction "5_5") (pintype "passive"))
    )
    (net (code "68") (name "unconnected-(TP1-Pad1)") (class "Default")
      (node (ref "TP1") (pin "1") (pinfunction "1_1") (pintype "passive"))
    )
    (net (code "69") (name "unconnected-(TP2-Pad1)") (class "Default")
      (node (ref "TP2") (pin "1") (pinfunction "1_1") (pintype "passive"))
    )
    (net (code "70") (name "unconnected-(TP3-Pad1)") (class "Default")
      (node (ref "TP3") (pin "1") (pinfunction "1_1") (pintype "passive"))
    )
    (net (code "71") (name "unconnected-(TP4-Pad1)") (class "Default")
      (node (ref "TP4") (pin "1") (pinfunction "1_1") (pintype "passive"))
    )
    (net (code "72") (name "unconnected-(TYPE-C1-CC1-PadA5)") (class "Default")
      (node (ref "TYPE-C1") (pin "A5") (pinfunction "CC1_A5") (pintype "passive"))
    )
    (net (code "73") (name "unconnected-(TYPE-C1-CC2-PadB5)") (class "Default")
      (node (ref "TYPE-C1") (pin "B5") (pinfunction "CC2_B5") (pintype "passive"))
    )
    (net (code "74") (name "unconnected-(TYPE-C1-SUB1-PadA8)") (class "Default")
      (node (ref "TYPE-C1") (pin "A8") (pinfunction "SUB1_A8") (pintype "passive"))
    )
    (net (code "75") (name "unconnected-(TYPE-C1-SUB2-PadB8)") (class "Default")
      (node (ref "TYPE-C1") (pin "B8") (pinfunction "SUB2_B8") (pintype "passive"))
    )
    (net (code "76") (name "unconnected-(U7-CTS-Pad23)") (class "Default")
      (node (ref "U7") (pin "23") (pinfunction "CTS_23") (pintype "passive"))
    )
    (net (code "77") (name "unconnected-(U7-DCD-Pad1)") (class "Default")
      (node (ref "U7") (pin "1") (pinfunction "DCD_1") (pintype "passive"))
    )
    (net (code "78") (name "unconnected-(U7-DSR-Pad27)") (class "Default")
      (node (ref "U7") (pin "27") (pinfunction "DSR_27") (pintype "passive"))
    )
    (net (code "79") (name "unconnected-(U7-EP-Pad29)") (class "Default")
      (node (ref "U7") (pin "29") (pinfunction "EP_29") (pintype "passive"))
    )
    (net (code "80") (name "unconnected-(U7-NC-Pad10)") (class "Default")
      (node (ref "U7") (pin "10") (pinfunction "NC_10") (pintype "passive"))
    )
    (net (code "81") (name "unconnected-(U7-NC-Pad13)") (class "Default")
      (node (ref "U7") (pin "13") (pinfunction "NC_13") (pintype "passive"))
    )
    (net (code "82") (name "unconnected-(U7-NC-Pad14)") (class "Default")
      (node (ref "U7") (pin "14") (pinfunction "NC_14") (pintype "passive"))
    )
    (net (code "83") (name "unconnected-(U7-NC-Pad15)") (class "Default")
      (node (ref "U7") (pin "15") (pinfunction "NC_15") (pintype "passive"))
    )
    (net (code "84") (name "unconnected-(U7-NC-Pad16)") (class "Default")
      (node (ref "U7") (pin "16") (pinfunction "NC_16") (pintype "passive"))
    )
    (net (code "85") (name "unconnected-(U7-NC-Pad17)") (class "Default")
      (node (ref "U7") (pin "17") (pinfunction "NC_17") (pintype "passive"))
    )
    (net (code "86") (name "unconnected-(U7-NC-Pad18)") (class "Default")
      (node (ref "U7") (pin "18") (pinfunction "NC_18") (pintype "passive"))
    )
    (net (code "87") (name "unconnected-(U7-NC-Pad19)") (class "Default")
      (node (ref "U7") (pin "19") (pinfunction "NC_19") (pintype "passive"))
    )
    (net (code "88") (name "unconnected-(U7-NC-Pad20)") (class "Default")
      (node (ref "U7") (pin "20") (pinfunction "NC_20") (pintype "passive"))
    )
    (net (code "89") (name "unconnected-(U7-NC-Pad21)") (class "Default")
      (node (ref "U7") (pin "21") (pinfunction "NC_21") (pintype "passive"))
    )
    (net (code "90") (name "unconnected-(U7-NC-Pad22)") (class "Default")
      (node (ref "U7") (pin "22") (pinfunction "NC_22") (pintype "passive"))
    )
    (net (code "91") (name "unconnected-(U7-RI-Pad2)") (class "Default")
      (node (ref "U7") (pin "2") (pinfunction "RI_2") (pintype "passive"))
    )
    (net (code "92") (name "unconnected-(U7-SUSPEND#-Pad11)") (class "Default")
      (node (ref "U7") (pin "11") (pinfunction "SUSPEND#_11") (pintype "passive"))
    )
    (net (code "93") (name "unconnected-(U7-SUSPEND-Pad12)") (class "Default")
      (node (ref "U7") (pin "12") (pinfunction "SUSPEND_12") (pintype "passive"))
    )
    (net (code "94") (name "unconnected-(U8-NC-Pad32)") (class "Default")
      (node (ref "U8") (pin "32") (pinfunction "NC_32") (pintype "passive"))
    )
  )
)
